# Sensor_LM35.net
KiCad netlist of a schematic drawn in Altium Designer
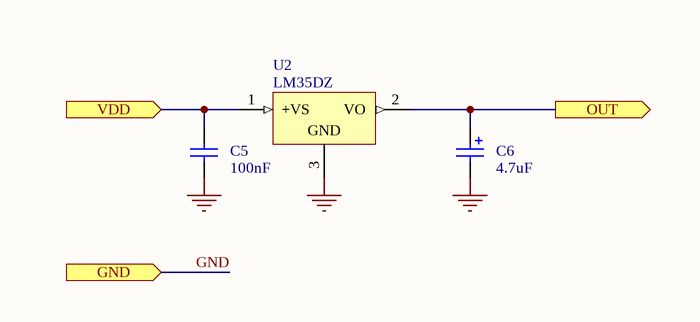
[diagram p0: Sensor_LM35.SchDoc]

(export (version "E")
  (design (tool "Eeschema 10.0.6"))
  (components
    (comp (ref "C5")
      (value "100nF")
      (footprint "CAPNTO5.08-7.37x3.94")
      (description "Capacitor")
      (fields
        (field (name "MANUFACTURER") "Generic Components")
        (field (name "Comment") "Cap")
        (field (name "PUBLISHER") "Altium Limited")
      )
      (libsource (lib "Miscellaneous Devices") (part "Cap"))
    )
    (comp (ref "C6")
      (value "4.7uF")
      (footprint "CAPPR2.5-6.3x5")
      (description "Polarized Capacitor (Radial)")
      (fields
        (field (name "MANUFACTURER") "Generic Components")
        (field (name "Comment") "Cap Pol1")
        (field (name "PUBLISHER") "Altium Limited")
      )
      (libsource (lib "Miscellaneous Devices") (part "Cap Pol1"))
    )
    (comp (ref "U2")
      (value "LM35DZ")
      (footprint "TO92C")
      (description "Precision Centigrade Temperature Sensor, 3-pin TO-92")
      (fields
        (field (name "MANUFACTURER") "National Semiconductor")
        (field (name "PUBLISHER") "Altium Limited")
      )
      (libsource (lib "NSC Temperature Sensor") (part "LM35DZ"))
    )
  )
  (nets
    (net (code "1") (name "/OUT") (class "Default")
      (node (ref "C6") (pin "1") (pinfunction "1_1") (pintype "passive"))
      (node (ref "U2") (pin "2") (pinfunction "VO_2") (pintype "output"))
    )
    (net (code "2") (name "/VDD") (class "Default")
      (node (ref "C5") (pin "2") (pinfunction "2_2") (pintype "passive"))
      (node (ref "U2") (pin "1") (pinfunction "+VS_1") (pintype "input"))
    )
    (net (code "3") (name "GND") (class "Default")
      (node (ref "C5") (pin "1") (pinfunction "1_1") (pintype "passive"))
      (node (ref "C6") (pin "2") (pinfunction "2_2") (pintype "passive"))
      (node (ref "U2") (pin "3") (pinfunction "GND_3") (pintype "power_in"))
    )
  )
)
